# Lights.net
KiCad netlist of a schematic drawn in Altium Designer
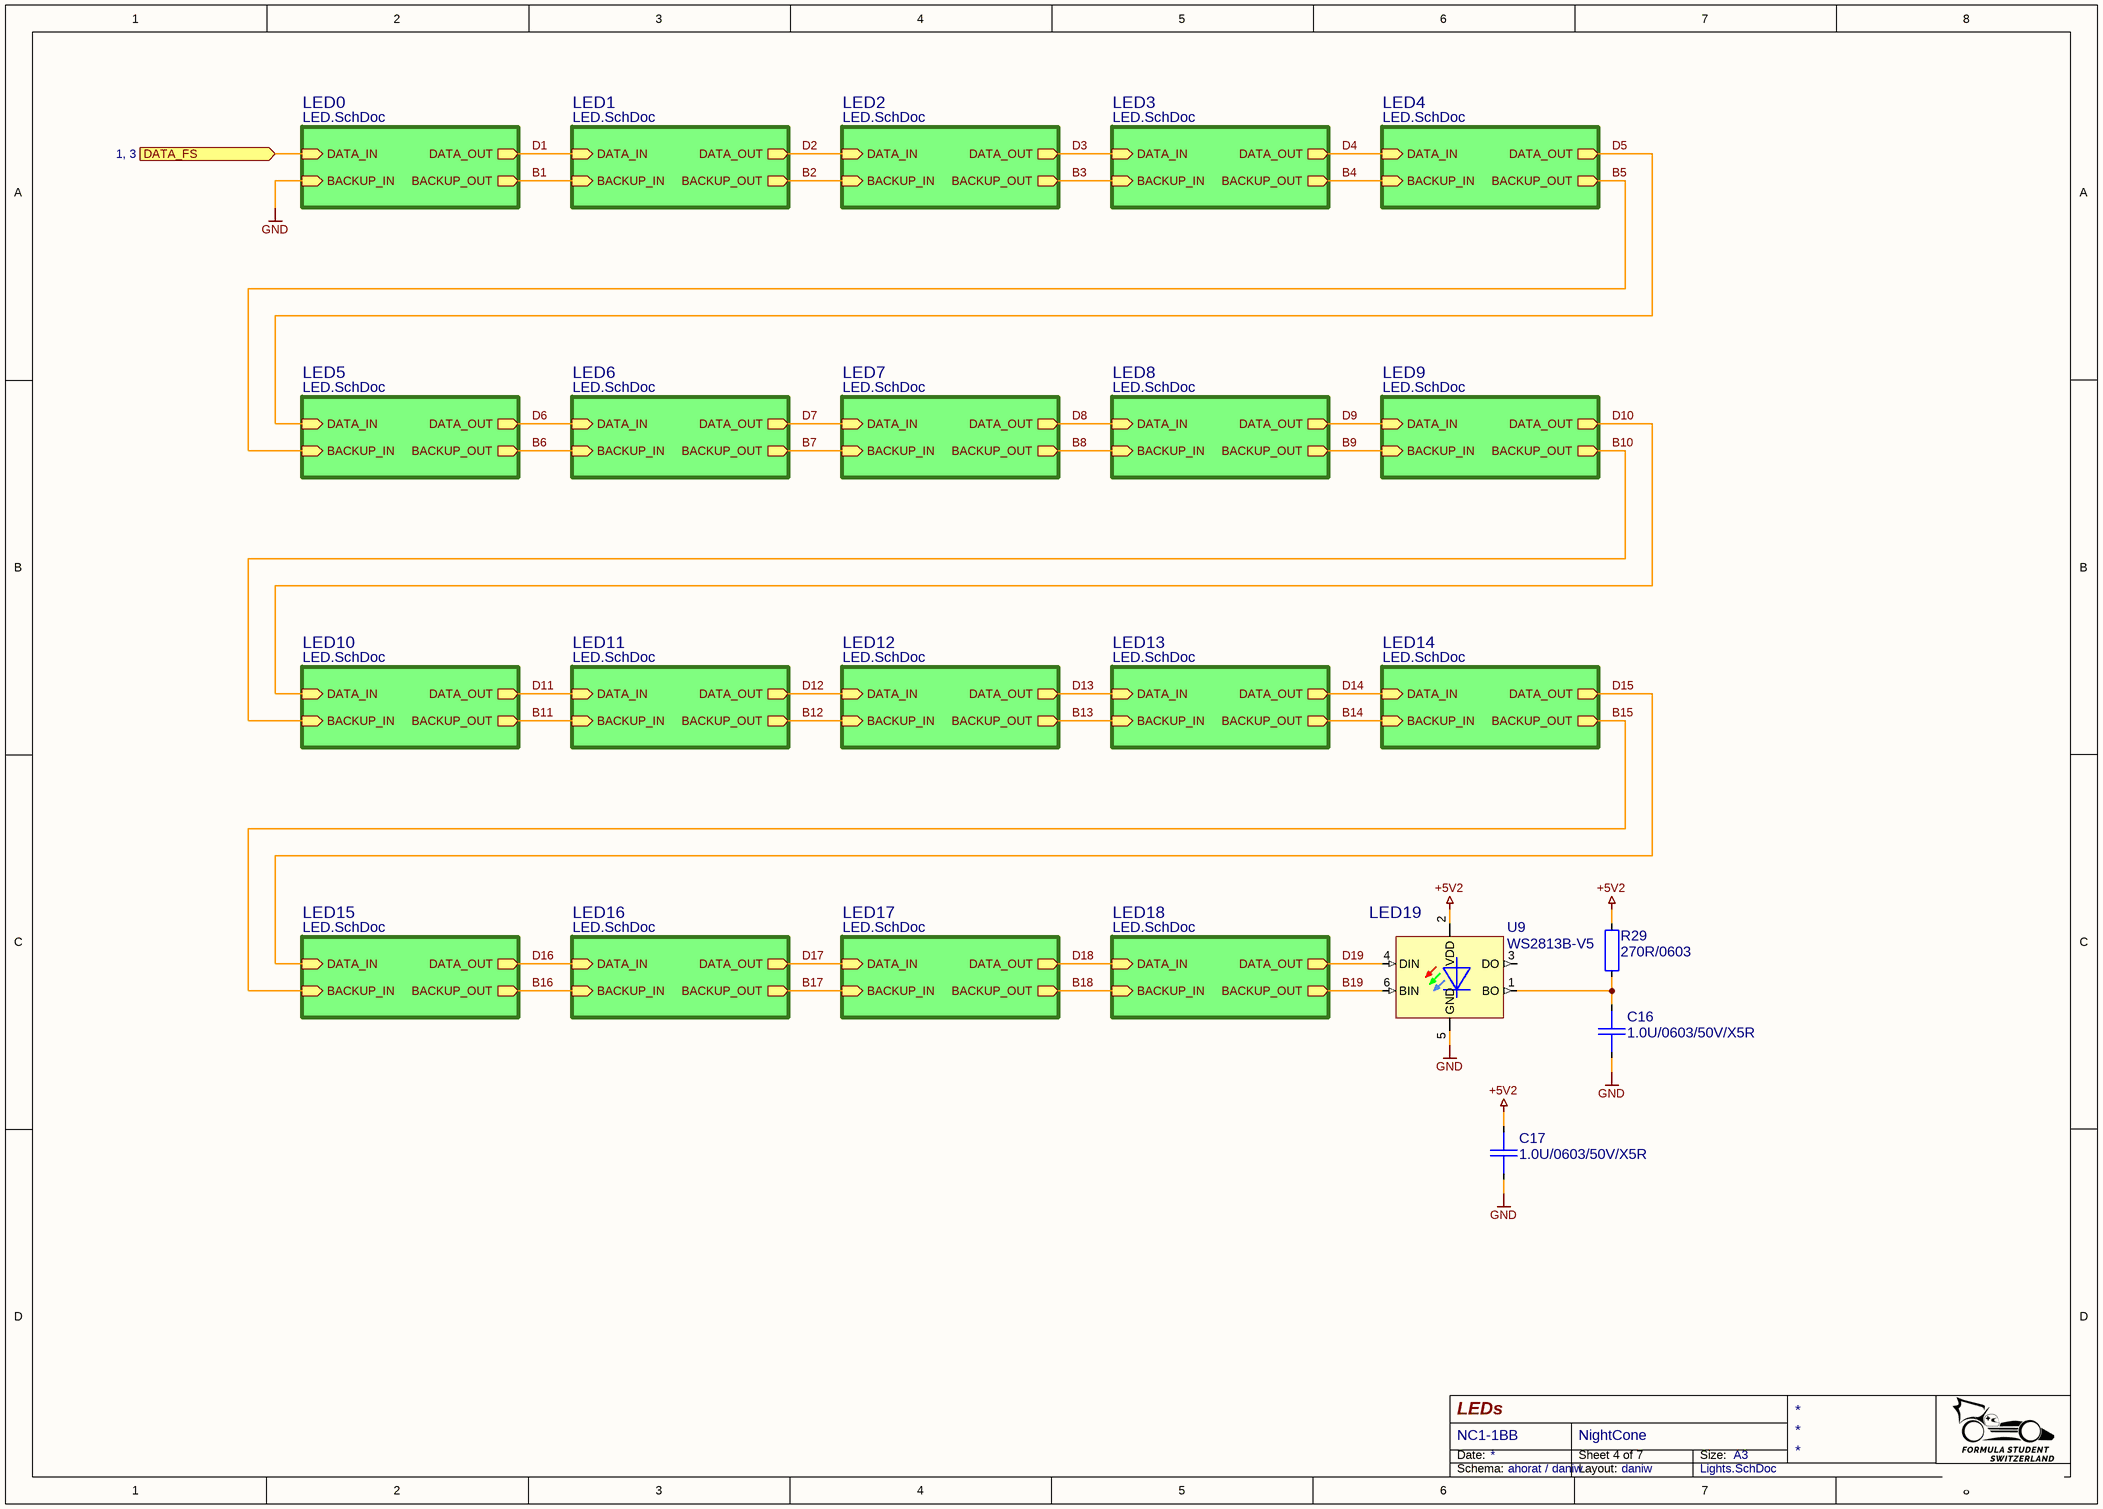
[diagram p0: Lights.SchDoc]

(export (version "E")
  (design (tool "Eeschema 10.0.6"))
  (components
    (comp (ref "C16")
      (value "1.0U/0603/50V/X5R")
      (footprint "CAP0603_X7R")
      (description "CAP SM 0603 1.0uF 50V X5R")
      (fields (field (name "MANUFACTURER") "GENERIC"))
      (libsource (lib "daniw_altium_lib") (part "C"))
    )
    (comp (ref "C17")
      (value "1.0U/0603/50V/X5R")
      (footprint "CAP0603_X7R")
      (description "CAP SM 0603 1.0uF 50V X5R")
      (fields (field (name "MANUFACTURER") "GENERIC"))
      (libsource (lib "daniw_altium_lib") (part "C"))
    )
    (comp (ref "R29")
      (value "270R/0603")
      (footprint "R0603-0.40-WW")
      (description "RES SM 0603 270R")
      (fields (field (name "MANUFACTURER") "GENERIC"))
      (libsource (lib "daniw_altium_lib") (part "R"))
    )
    (comp (ref "U9")
      (value "WS2813B-V5")
      (footprint "LEDM5050X165-6-SE")
      (description "Intelligent control LED integrated light source with backup Pin")
      (fields (field (name "MANUFACTURER") "WorldSemi"))
      (libsource (lib "daniw_altium_lib") (part "WS2813_BO"))
    )
  )
  (nets
    (net (code "1") (name "+5V2") (class "Default")
      (node (ref "C17") (pin "1") (pinfunction "1_1") (pintype "passive"))
      (node (ref "R29") (pin "1") (pinfunction "1_1") (pintype "passive"))
      (node (ref "U9") (pin "2") (pinfunction "VDD_2") (pintype "passive"))
    )
    (net (code "20") (name "/B19") (class "Default")
      (node (ref "U9") (pin "6") (pinfunction "BIN_6") (pintype "input"))
    )
    (net (code "39") (name "/D19") (class "Default")
      (node (ref "U9") (pin "4") (pinfunction "DIN_4") (pintype "input"))
    )
    (net (code "41") (name "GND") (class "Default")
      (node (ref "C16") (pin "2") (pinfunction "2_2") (pintype "passive"))
      (node (ref "C17") (pin "2") (pinfunction "2_2") (pintype "passive"))
      (node (ref "U9") (pin "5") (pinfunction "GND_5") (pintype "passive"))
    )
    (net (code "42") (name "Net-(U9-BO)") (class "Default")
      (node (ref "C16") (pin "1") (pinfunction "1_1") (pintype "passive"))
      (node (ref "R29") (pin "2") (pinfunction "2_2") (pintype "passive"))
      (node (ref "U9") (pin "1") (pinfunction "BO_1") (pintype "output"))
    )
    (net (code "43") (name "unconnected-(U9-DO-Pad3)") (class "Default")
      (node (ref "U9") (pin "3") (pinfunction "DO_3") (pintype "output"))
    )
  )
)
